# fpga-shield-v1_0.net
KiCad netlist of a schematic drawn in EAGLE
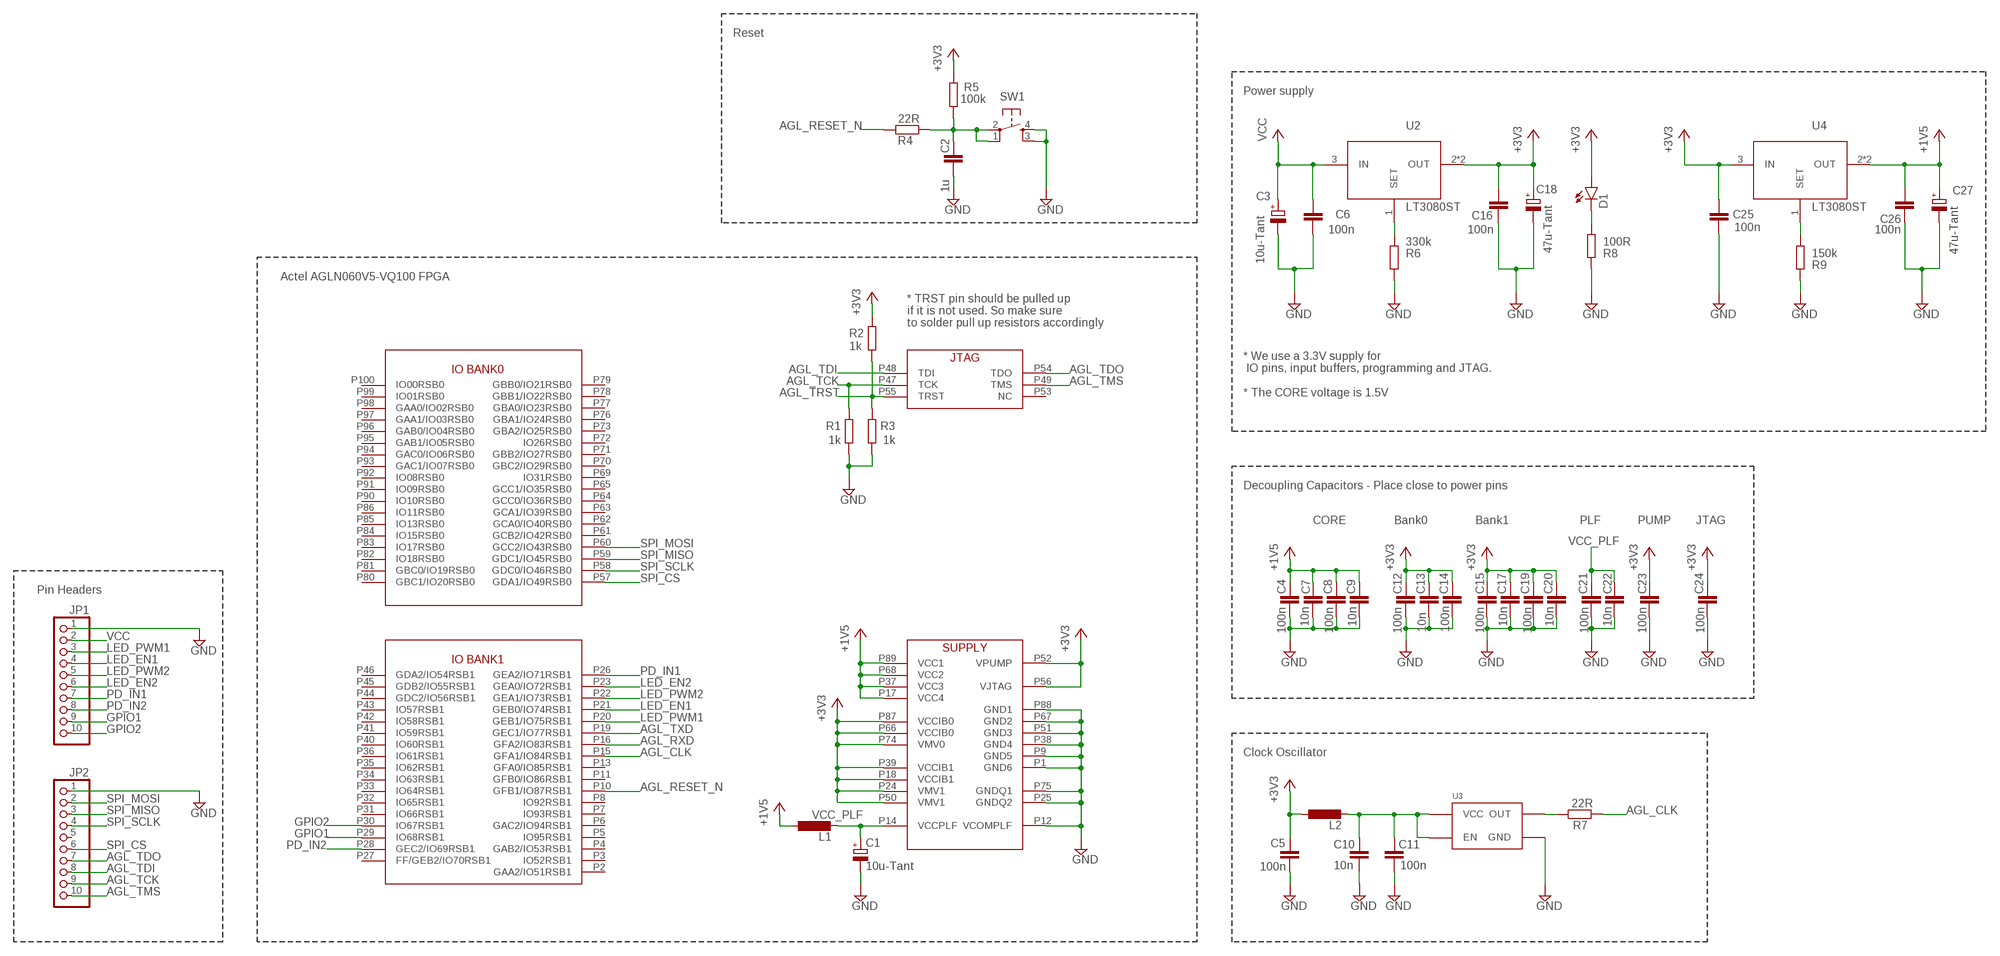
[diagram p0: schematic, sheet 1]

(export (version "E")
  (design (tool "Eeschema 10.0.6"))
  (components
    (comp (ref "C1")
      (value "10u-Tant")
      (footprint "eagle-import:CT3528")
      (libsource (lib "eagle-import") (part "CPOL-EUCT3528"))
    )
    (comp (ref "C2")
      (value "1u")
      (footprint "eagle-import:C0805")
      (libsource (lib "eagle-import") (part "C-EUC0805"))
    )
    (comp (ref "C3")
      (value "10u-Tant")
      (footprint "eagle-import:CT3528")
      (libsource (lib "eagle-import") (part "CPOL-EUCT3528"))
    )
    (comp (ref "C4")
      (value "100n")
      (footprint "eagle-import:C0805")
      (libsource (lib "eagle-import") (part "C-EUC0805"))
    )
    (comp (ref "C5")
      (value "100n")
      (footprint "eagle-import:C0805")
      (libsource (lib "eagle-import") (part "C-EUC0805"))
    )
    (comp (ref "C6")
      (value "100n")
      (footprint "eagle-import:C0805")
      (libsource (lib "eagle-import") (part "C-EUC0805"))
    )
    (comp (ref "C7")
      (value "10n")
      (footprint "eagle-import:C0805")
      (libsource (lib "eagle-import") (part "C-EUC0805"))
    )
    (comp (ref "C8")
      (value "100n")
      (footprint "eagle-import:C0805")
      (libsource (lib "eagle-import") (part "C-EUC0805"))
    )
    (comp (ref "C9")
      (value "10n")
      (footprint "eagle-import:C0805")
      (libsource (lib "eagle-import") (part "C-EUC0805"))
    )
    (comp (ref "C10")
      (value "10n")
      (footprint "eagle-import:C0805")
      (libsource (lib "eagle-import") (part "C-EUC0805"))
    )
    (comp (ref "C11")
      (value "100n")
      (footprint "eagle-import:C0805")
      (libsource (lib "eagle-import") (part "C-EUC0805"))
    )
    (comp (ref "C12")
      (value "100n")
      (footprint "eagle-import:C0805")
      (libsource (lib "eagle-import") (part "C-EUC0805"))
    )
    (comp (ref "C13")
      (value "10n")
      (footprint "eagle-import:C0805")
      (libsource (lib "eagle-import") (part "C-EUC0805"))
    )
    (comp (ref "C14")
      (value "100n")
      (footprint "eagle-import:C0805")
      (libsource (lib "eagle-import") (part "C-EUC0805"))
    )
    (comp (ref "C15")
      (value "100n")
      (footprint "eagle-import:C0805")
      (libsource (lib "eagle-import") (part "C-EUC0805"))
    )
    (comp (ref "C16")
      (value "100n")
      (footprint "eagle-import:C0805")
      (libsource (lib "eagle-import") (part "C-EUC0805"))
    )
    (comp (ref "C17")
      (value "10n")
      (footprint "eagle-import:C0805")
      (libsource (lib "eagle-import") (part "C-EUC0805"))
    )
    (comp (ref "C18")
      (value "47u-Tant")
      (footprint "eagle-import:CT3528")
      (libsource (lib "eagle-import") (part "CPOL-EUCT3528"))
    )
    (comp (ref "C19")
      (value "100n")
      (footprint "eagle-import:C0805")
      (libsource (lib "eagle-import") (part "C-EUC0805"))
    )
    (comp (ref "C20")
      (value "10n")
      (footprint "eagle-import:C0805")
      (libsource (lib "eagle-import") (part "C-EUC0805"))
    )
    (comp (ref "C21")
      (value "100n")
      (footprint "eagle-import:C0805")
      (libsource (lib "eagle-import") (part "C-EUC0805"))
    )
    (comp (ref "C22")
      (value "10n")
      (footprint "eagle-import:C0805")
      (libsource (lib "eagle-import") (part "C-EUC0805"))
    )
    (comp (ref "C23")
      (value "100n")
      (footprint "eagle-import:C0805")
      (libsource (lib "eagle-import") (part "C-EUC0805"))
    )
    (comp (ref "C24")
      (value "100n")
      (footprint "eagle-import:C0805")
      (libsource (lib "eagle-import") (part "C-EUC0805"))
    )
    (comp (ref "C25")
      (value "100n")
      (footprint "eagle-import:C0805")
      (libsource (lib "eagle-import") (part "C-EUC0805"))
    )
    (comp (ref "C26")
      (value "100n")
      (footprint "eagle-import:C0805")
      (libsource (lib "eagle-import") (part "C-EUC0805"))
    )
    (comp (ref "C27")
      (value "47u-Tant")
      (footprint "eagle-import:CT3528")
      (libsource (lib "eagle-import") (part "CPOL-EUCT3528"))
    )
    (comp (ref "D1")
      (value "LED0603")
      (footprint "eagle-import:LED-0603")
      (libsource (lib "eagle-import") (part "LED0603"))
    )
    (comp (ref "JP1")
      (value "PINHD-1X10")
      (footprint "eagle-import:1X10")
      (libsource (lib "eagle-import") (part "PINHD-1X10"))
    )
    (comp (ref "JP2")
      (value "PINHD-1X10")
      (footprint "eagle-import:1X10")
      (libsource (lib "eagle-import") (part "PINHD-1X10"))
    )
    (comp (ref "L1")
      (value "L-EUL3216C")
      (footprint "eagle-import:L3216C")
      (libsource (lib "eagle-import") (part "L-EUL3216C"))
    )
    (comp (ref "L2")
      (value "L-EUL3216C")
      (footprint "eagle-import:L3216C")
      (libsource (lib "eagle-import") (part "L-EUL3216C"))
    )
    (comp (ref "R1")
      (value "1k")
      (footprint "eagle-import:R0805")
      (libsource (lib "eagle-import") (part "R-EU_R0805"))
    )
    (comp (ref "R2")
      (value "1k")
      (footprint "eagle-import:R0805")
      (libsource (lib "eagle-import") (part "R-EU_R0805"))
    )
    (comp (ref "R3")
      (value "1k")
      (footprint "eagle-import:R0805")
      (libsource (lib "eagle-import") (part "R-EU_R0805"))
    )
    (comp (ref "R4")
      (value "22R")
      (footprint "eagle-import:R0805")
      (libsource (lib "eagle-import") (part "R-EU_R0805"))
    )
    (comp (ref "R5")
      (value "100k")
      (footprint "eagle-import:R0805")
      (libsource (lib "eagle-import") (part "R-EU_R0805"))
    )
    (comp (ref "R6")
      (value "330k")
      (footprint "eagle-import:R0805")
      (libsource (lib "eagle-import") (part "R-EU_R0805"))
    )
    (comp (ref "R7")
      (value "22R")
      (footprint "eagle-import:R0805")
      (libsource (lib "eagle-import") (part "R-EU_R0805"))
    )
    (comp (ref "R8")
      (value "100R")
      (footprint "eagle-import:R0805")
      (libsource (lib "eagle-import") (part "R-EU_R0805"))
    )
    (comp (ref "R9")
      (value "150k")
      (footprint "eagle-import:R0805")
      (libsource (lib "eagle-import") (part "R-EU_R0805"))
    )
    (comp (ref "SW1")
      (value "10-XX4X4SMD")
      (footprint "eagle-import:BT4X4")
      (libsource (lib "eagle-import") (part "10-XX4X4SMD"))
    )
    (comp (ref "U1")
      (value "AGLN060VQ100")
      (footprint "eagle-import:VQ100")
      (libsource (lib "eagle-import") (part "AGLN060VQ100"))
    )
    (comp (ref "U2")
      (value "LT3080ST")
      (footprint "eagle-import:SOT223")
      (libsource (lib "eagle-import") (part "LT3080ST"))
    )
    (comp (ref "U3")
      (value "ASFL1")
      (footprint "eagle-import:ASFL1")
      (libsource (lib "eagle-import") (part "ASFL1"))
    )
    (comp (ref "U4")
      (value "LT3080ST")
      (footprint "eagle-import:SOT223")
      (libsource (lib "eagle-import") (part "LT3080ST"))
    )
  )
  (nets
    (net (code "1") (name "+1V5") (class "Default")
      (node (ref "C26") (pin "1") (pinfunction "1_1") (pintype "passive"))
      (node (ref "C27") (pin "+") (pinfunction "+_+") (pintype "passive"))
      (node (ref "C4") (pin "1") (pinfunction "1_1") (pintype "passive"))
      (node (ref "C7") (pin "1") (pinfunction "1_1") (pintype "passive"))
      (node (ref "C8") (pin "1") (pinfunction "1_1") (pintype "passive"))
      (node (ref "C9") (pin "1") (pinfunction "1_1") (pintype "passive"))
      (node (ref "L1") (pin "1") (pinfunction "1_1") (pintype "passive"))
      (node (ref "U1") (pin "P17") (pinfunction "VCC4_P17") (pintype "power_in"))
      (node (ref "U1") (pin "P37") (pinfunction "VCC3_P37") (pintype "power_in"))
      (node (ref "U1") (pin "P68") (pinfunction "VCC2_P68") (pintype "power_in"))
      (node (ref "U1") (pin "P89") (pinfunction "VCC1_P89") (pintype "power_in"))
      (node (ref "U4") (pin "2") (pinfunction "OUT_2") (pintype "passive"))
      (node (ref "U4") (pin "4") (pinfunction "OUT_4") (pintype "passive"))
    )
    (net (code "2") (name "+3V3") (class "Default")
      (node (ref "C12") (pin "1") (pinfunction "1_1") (pintype "passive"))
      (node (ref "C13") (pin "1") (pinfunction "1_1") (pintype "passive"))
      (node (ref "C14") (pin "1") (pinfunction "1_1") (pintype "passive"))
      (node (ref "C15") (pin "1") (pinfunction "1_1") (pintype "passive"))
      (node (ref "C16") (pin "1") (pinfunction "1_1") (pintype "passive"))
      (node (ref "C17") (pin "1") (pinfunction "1_1") (pintype "passive"))
      (node (ref "C18") (pin "+") (pinfunction "+_+") (pintype "passive"))
      (node (ref "C19") (pin "1") (pinfunction "1_1") (pintype "passive"))
      (node (ref "C20") (pin "1") (pinfunction "1_1") (pintype "passive"))
      (node (ref "C23") (pin "1") (pinfunction "1_1") (pintype "passive"))
      (node (ref "C24") (pin "1") (pinfunction "1_1") (pintype "passive"))
      (node (ref "C25") (pin "1") (pinfunction "1_1") (pintype "passive"))
      (node (ref "C5") (pin "1") (pinfunction "1_1") (pintype "passive"))
      (node (ref "D1") (pin "A") (pinfunction "A_A") (pintype "passive"))
      (node (ref "L2") (pin "1") (pinfunction "1_1") (pintype "passive"))
      (node (ref "R2") (pin "2") (pinfunction "2_2") (pintype "passive"))
      (node (ref "R5") (pin "2") (pinfunction "2_2") (pintype "passive"))
      (node (ref "U1") (pin "P18") (pinfunction "VCCIB1_P18") (pintype "power_in"))
      (node (ref "U1") (pin "P24") (pinfunction "VMV1_P24") (pintype "power_in"))
      (node (ref "U1") (pin "P39") (pinfunction "VCCIB1_P39") (pintype "power_in"))
      (node (ref "U1") (pin "P50") (pinfunction "VMV1_P50") (pintype "power_in"))
      (node (ref "U1") (pin "P52") (pinfunction "VPUMP_P52") (pintype "power_in"))
      (node (ref "U1") (pin "P56") (pinfunction "VJTAG_P56") (pintype "power_in"))
      (node (ref "U1") (pin "P66") (pinfunction "VCCIB0_P66") (pintype "power_in"))
      (node (ref "U1") (pin "P74") (pinfunction "VMV0_P74") (pintype "power_in"))
      (node (ref "U1") (pin "P87") (pinfunction "VCCIB0_P87") (pintype "power_in"))
      (node (ref "U2") (pin "2") (pinfunction "OUT_2") (pintype "passive"))
      (node (ref "U2") (pin "4") (pinfunction "OUT_4") (pintype "passive"))
      (node (ref "U4") (pin "3") (pinfunction "IN_3") (pintype "power_in"))
    )
    (net (code "3") (name "/AGL_CLK") (class "Default")
      (node (ref "R7") (pin "2") (pinfunction "2_2") (pintype "passive"))
      (node (ref "U1") (pin "P15") (pinfunction "GFA1/IO84RSB1_P15") (pintype "bidirectional"))
    )
    (net (code "4") (name "/AGL_RESET_N") (class "Default")
      (node (ref "R4") (pin "2") (pinfunction "2_2") (pintype "passive"))
      (node (ref "U1") (pin "P10") (pinfunction "GFB1/IO87RSB1_P10") (pintype "bidirectional"))
    )
    (net (code "5") (name "/AGL_RXD") (class "Default")
      (node (ref "U1") (pin "P16") (pinfunction "GFA2/IO83RSB1_P16") (pintype "bidirectional"))
    )
    (net (code "6") (name "/AGL_TCK") (class "Default")
      (node (ref "JP2") (pin "9") (pinfunction "9_9") (pintype "passive"))
      (node (ref "R1") (pin "2") (pinfunction "2_2") (pintype "passive"))
      (node (ref "U1") (pin "P47") (pinfunction "TCK_P47") (pintype "input"))
    )
    (net (code "7") (name "/AGL_TDI") (class "Default")
      (node (ref "JP2") (pin "8") (pinfunction "8_8") (pintype "passive"))
      (node (ref "U1") (pin "P48") (pinfunction "TDI_P48") (pintype "input"))
    )
    (net (code "8") (name "/AGL_TDO") (class "Default")
      (node (ref "JP2") (pin "7") (pinfunction "7_7") (pintype "passive"))
      (node (ref "U1") (pin "P54") (pinfunction "TDO_P54") (pintype "output"))
    )
    (net (code "9") (name "/AGL_TMS") (class "Default")
      (node (ref "JP2") (pin "10") (pinfunction "10_10") (pintype "passive"))
      (node (ref "U1") (pin "P49") (pinfunction "TMS_P49") (pintype "input"))
    )
    (net (code "10") (name "/AGL_TRST") (class "Default")
      (node (ref "R2") (pin "1") (pinfunction "1_1") (pintype "passive"))
      (node (ref "R3") (pin "2") (pinfunction "2_2") (pintype "passive"))
      (node (ref "U1") (pin "P55") (pinfunction "TRST_P55") (pintype "input"))
    )
    (net (code "11") (name "/AGL_TXD") (class "Default")
      (node (ref "U1") (pin "P19") (pinfunction "GEC1/IO77RSB1_P19") (pintype "bidirectional"))
    )
    (net (code "12") (name "/GPIO1") (class "Default")
      (node (ref "JP1") (pin "9") (pinfunction "9_9") (pintype "passive"))
      (node (ref "U1") (pin "P29") (pinfunction "IO68RSB1_P29") (pintype "bidirectional"))
    )
    (net (code "13") (name "/GPIO2") (class "Default")
      (node (ref "JP1") (pin "10") (pinfunction "10_10") (pintype "passive"))
      (node (ref "U1") (pin "P30") (pinfunction "IO67RSB1_P30") (pintype "bidirectional"))
    )
    (net (code "14") (name "/LED_EN1") (class "Default")
      (node (ref "JP1") (pin "4") (pinfunction "4_4") (pintype "passive"))
      (node (ref "U1") (pin "P21") (pinfunction "GEB0/IO74RSB1_P21") (pintype "bidirectional"))
    )
    (net (code "15") (name "/LED_EN2") (class "Default")
      (node (ref "JP1") (pin "6") (pinfunction "6_6") (pintype "passive"))
      (node (ref "U1") (pin "P23") (pinfunction "GEA0/IO72RSB1_P23") (pintype "bidirectional"))
    )
    (net (code "16") (name "/LED_PWM1") (class "Default")
      (node (ref "JP1") (pin "3") (pinfunction "3_3") (pintype "passive"))
      (node (ref "U1") (pin "P20") (pinfunction "GEB1/IO75RSB1_P20") (pintype "bidirectional"))
    )
    (net (code "17") (name "/LED_PWM2") (class "Default")
      (node (ref "JP1") (pin "5") (pinfunction "5_5") (pintype "passive"))
      (node (ref "U1") (pin "P22") (pinfunction "GEA1/IO73RSB1_P22") (pintype "bidirectional"))
    )
    (net (code "18") (name "/PD_IN1") (class "Default")
      (node (ref "JP1") (pin "7") (pinfunction "7_7") (pintype "passive"))
      (node (ref "U1") (pin "P26") (pinfunction "GEA2/IO71RSB1_P26") (pintype "bidirectional"))
    )
    (net (code "19") (name "/PD_IN2") (class "Default")
      (node (ref "JP1") (pin "8") (pinfunction "8_8") (pintype "passive"))
      (node (ref "U1") (pin "P28") (pinfunction "GEC2/IO69RSB1_P28") (pintype "bidirectional"))
    )
    (net (code "20") (name "/SPI_CS") (class "Default")
      (node (ref "JP2") (pin "6") (pinfunction "6_6") (pintype "passive"))
      (node (ref "U1") (pin "P57") (pinfunction "GDA1/IO49RSB0_P57") (pintype "bidirectional"))
    )
    (net (code "21") (name "/SPI_MISO") (class "Default")
      (node (ref "JP2") (pin "3") (pinfunction "3_3") (pintype "passive"))
      (node (ref "U1") (pin "P59") (pinfunction "GDC1/IO45RSB0_P59") (pintype "bidirectional"))
    )
    (net (code "22") (name "/SPI_MOSI") (class "Default")
      (node (ref "JP2") (pin "2") (pinfunction "2_2") (pintype "passive"))
      (node (ref "U1") (pin "P60") (pinfunction "GCC2/IO43RSB0_P60") (pintype "bidirectional"))
    )
    (net (code "23") (name "/SPI_SCLK") (class "Default")
      (node (ref "JP2") (pin "4") (pinfunction "4_4") (pintype "passive"))
      (node (ref "U1") (pin "P58") (pinfunction "GDC0/IO46RSB0_P58") (pintype "bidirectional"))
    )
    (net (code "24") (name "/VCC_PLF") (class "Default")
      (node (ref "C1") (pin "+") (pinfunction "+_+") (pintype "passive"))
      (node (ref "C21") (pin "1") (pinfunction "1_1") (pintype "passive"))
      (node (ref "C22") (pin "1") (pinfunction "1_1") (pintype "passive"))
      (node (ref "L1") (pin "2") (pinfunction "2_2") (pintype "passive"))
      (node (ref "U1") (pin "P14") (pinfunction "VCCPLF_P14") (pintype "power_in"))
    )
    (net (code "25") (name "GND") (class "Default")
      (node (ref "C1") (pin "-") (pinfunction "-_-") (pintype "passive"))
      (node (ref "C10") (pin "2") (pinfunction "2_2") (pintype "passive"))
      (node (ref "C11") (pin "2") (pinfunction "2_2") (pintype "passive"))
      (node (ref "C12") (pin "2") (pinfunction "2_2") (pintype "passive"))
      (node (ref "C13") (pin "2") (pinfunction "2_2") (pintype "passive"))
      (node (ref "C14") (pin "2") (pinfunction "2_2") (pintype "passive"))
      (node (ref "C15") (pin "2") (pinfunction "2_2") (pintype "passive"))
      (node (ref "C16") (pin "2") (pinfunction "2_2") (pintype "passive"))
      (node (ref "C17") (pin "2") (pinfunction "2_2") (pintype "passive"))
      (node (ref "C18") (pin "-") (pinfunction "-_-") (pintype "passive"))
      (node (ref "C19") (pin "2") (pinfunction "2_2") (pintype "passive"))
      (node (ref "C2") (pin "2") (pinfunction "2_2") (pintype "passive"))
      (node (ref "C20") (pin "2") (pinfunction "2_2") (pintype "passive"))
      (node (ref "C21") (pin "2") (pinfunction "2_2") (pintype "passive"))
      (node (ref "C22") (pin "2") (pinfunction "2_2") (pintype "passive"))
      (node (ref "C23") (pin "2") (pinfunction "2_2") (pintype "passive"))
      (node (ref "C24") (pin "2") (pinfunction "2_2") (pintype "passive"))
      (node (ref "C25") (pin "2") (pinfunction "2_2") (pintype "passive"))
      (node (ref "C26") (pin "2") (pinfunction "2_2") (pintype "passive"))
      (node (ref "C27") (pin "-") (pinfunction "-_-") (pintype "passive"))
      (node (ref "C3") (pin "-") (pinfunction "-_-") (pintype "passive"))
      (node (ref "C4") (pin "2") (pinfunction "2_2") (pintype "passive"))
      (node (ref "C5") (pin "2") (pinfunction "2_2") (pintype "passive"))
      (node (ref "C6") (pin "2") (pinfunction "2_2") (pintype "passive"))
      (node (ref "C7") (pin "2") (pinfunction "2_2") (pintype "passive"))
      (node (ref "C8") (pin "2") (pinfunction "2_2") (pintype "passive"))
      (node (ref "C9") (pin "2") (pinfunction "2_2") (pintype "passive"))
      (node (ref "JP1") (pin "1") (pinfunction "1_1") (pintype "passive"))
      (node (ref "JP2") (pin "1") (pinfunction "1_1") (pintype "passive"))
      (node (ref "R1") (pin "1") (pinfunction "1_1") (pintype "passive"))
      (node (ref "R3") (pin "1") (pinfunction "1_1") (pintype "passive"))
      (node (ref "R6") (pin "2") (pinfunction "2_2") (pintype "passive"))
      (node (ref "R8") (pin "2") (pinfunction "2_2") (pintype "passive"))
      (node (ref "R9") (pin "2") (pinfunction "2_2") (pintype "passive"))
      (node (ref "SW1") (pin "3") (pinfunction "S1_3") (pintype "passive"))
      (node (ref "SW1") (pin "4") (pinfunction "S_4") (pintype "passive"))
      (node (ref "U1") (pin "P1") (pinfunction "GND6_P1") (pintype "power_in"))
      (node (ref "U1") (pin "P12") (pinfunction "VCOMPLF_P12") (pintype "power_in"))
      (node (ref "U1") (pin "P25") (pinfunction "GNDQ2_P25") (pintype "power_in"))
      (node (ref "U1") (pin "P38") (pinfunction "GND4_P38") (pintype "power_in"))
      (node (ref "U1") (pin "P51") (pinfunction "GND3_P51") (pintype "power_in"))
      (node (ref "U1") (pin "P67") (pinfunction "GND2_P67") (pintype "power_in"))
      (node (ref "U1") (pin "P75") (pinfunction "GNDQ1_P75") (pintype "power_in"))
      (node (ref "U1") (pin "P88") (pinfunction "GND1_P88") (pintype "power_in"))
      (node (ref "U1") (pin "P9") (pinfunction "GND5_P9") (pintype "power_in"))
      (node (ref "U3") (pin "P$2") (pinfunction "GND_P$2") (pintype "bidirectional"))
    )
    (net (code "26") (name "Net-(D1-PadC)") (class "Default")
      (node (ref "D1") (pin "C") (pinfunction "C_C") (pintype "passive"))
      (node (ref "R8") (pin "1") (pinfunction "1_1") (pintype "passive"))
    )
    (net (code "27") (name "Net-(SW1-P)") (class "Default")
      (node (ref "C2") (pin "1") (pinfunction "1_1") (pintype "passive"))
      (node (ref "R4") (pin "1") (pinfunction "1_1") (pintype "passive"))
      (node (ref "R5") (pin "1") (pinfunction "1_1") (pintype "passive"))
      (node (ref "SW1") (pin "1") (pinfunction "P1_1") (pintype "passive"))
      (node (ref "SW1") (pin "2") (pinfunction "P_2") (pintype "passive"))
    )
    (net (code "28") (name "Net-(U2-SET)") (class "Default")
      (node (ref "R6") (pin "1") (pinfunction "1_1") (pintype "passive"))
      (node (ref "U2") (pin "1") (pinfunction "SET_1") (pintype "passive"))
    )
    (net (code "29") (name "Net-(U3-EN)") (class "Default")
      (node (ref "C10") (pin "1") (pinfunction "1_1") (pintype "passive"))
      (node (ref "C11") (pin "1") (pinfunction "1_1") (pintype "passive"))
      (node (ref "L2") (pin "2") (pinfunction "2_2") (pintype "passive"))
      (node (ref "U3") (pin "P$1") (pinfunction "EN_P$1") (pintype "bidirectional"))
      (node (ref "U3") (pin "P$4") (pinfunction "VCC_P$4") (pintype "bidirectional"))
    )
    (net (code "30") (name "Net-(U3-OUT)") (class "Default")
      (node (ref "R7") (pin "1") (pinfunction "1_1") (pintype "passive"))
      (node (ref "U3") (pin "P$3") (pinfunction "OUT_P$3") (pintype "bidirectional"))
    )
    (net (code "31") (name "Net-(U4-SET)") (class "Default")
      (node (ref "R9") (pin "1") (pinfunction "1_1") (pintype "passive"))
      (node (ref "U4") (pin "1") (pinfunction "SET_1") (pintype "passive"))
    )
    (net (code "32") (name "VCC") (class "Default")
      (node (ref "C3") (pin "+") (pinfunction "+_+") (pintype "passive"))
      (node (ref "C6") (pin "1") (pinfunction "1_1") (pintype "passive"))
      (node (ref "JP1") (pin "2") (pinfunction "2_2") (pintype "passive"))
      (node (ref "U2") (pin "3") (pinfunction "IN_3") (pintype "power_in"))
    )
    (net (code "33") (name "unconnected-(JP2-Pad5)") (class "Default")
      (node (ref "JP2") (pin "5") (pinfunction "5_5") (pintype "passive"))
    )
    (net (code "34") (name "unconnected-(U1A-GAA0{slash}IO02RSB0-PadP98)") (class "Default")
      (node (ref "U1") (pin "P98") (pinfunction "GAA0/IO02RSB0_P98") (pintype "bidirectional"))
    )
    (net (code "35") (name "unconnected-(U1A-GAA1{slash}IO03RSB0-PadP97)") (class "Default")
      (node (ref "U1") (pin "P97") (pinfunction "GAA1/IO03RSB0_P97") (pintype "bidirectional"))
    )
    (net (code "36") (name "unconnected-(U1A-GAB0{slash}IO04RSB0-PadP96)") (class "Default")
      (node (ref "U1") (pin "P96") (pinfunction "GAB0/IO04RSB0_P96") (pintype "bidirectional"))
    )
    (net (code "37") (name "unconnected-(U1A-GAB1{slash}IO05RSB0-PadP95)") (class "Default")
      (node (ref "U1") (pin "P95") (pinfunction "GAB1/IO05RSB0_P95") (pintype "bidirectional"))
    )
    (net (code "38") (name "unconnected-(U1A-GAC0{slash}IO06RSB0-PadP94)") (class "Default")
      (node (ref "U1") (pin "P94") (pinfunction "GAC0/IO06RSB0_P94") (pintype "bidirectional"))
    )
    (net (code "39") (name "unconnected-(U1A-GAC1{slash}IO07RSB0-PadP93)") (class "Default")
      (node (ref "U1") (pin "P93") (pinfunction "GAC1/IO07RSB0_P93") (pintype "bidirectional"))
    )
    (net (code "40") (name "unconnected-(U1A-GBA0{slash}IO23RSB0-PadP77)") (class "Default")
      (node (ref "U1") (pin "P77") (pinfunction "GBA0/IO23RSB0_P77") (pintype "bidirectional"))
    )
    (net (code "41") (name "unconnected-(U1A-GBA1{slash}IO24RSB0-PadP76)") (class "Default")
      (node (ref "U1") (pin "P76") (pinfunction "GBA1/IO24RSB0_P76") (pintype "bidirectional"))
    )
    (net (code "42") (name "unconnected-(U1A-GBA2{slash}IO25RSB0-PadP73)") (class "Default")
      (node (ref "U1") (pin "P73") (pinfunction "GBA2/IO25RSB0_P73") (pintype "bidirectional"))
    )
    (net (code "43") (name "unconnected-(U1A-GBB0{slash}IO21RSB0-PadP79)") (class "Default")
      (node (ref "U1") (pin "P79") (pinfunction "GBB0/IO21RSB0_P79") (pintype "bidirectional"))
    )
    (net (code "44") (name "unconnected-(U1A-GBB1{slash}IO22RSB0-PadP78)") (class "Default")
      (node (ref "U1") (pin "P78") (pinfunction "GBB1/IO22RSB0_P78") (pintype "bidirectional"))
    )
    (net (code "45") (name "unconnected-(U1A-GBB2{slash}IO27RSB0-PadP71)") (class "Default")
      (node (ref "U1") (pin "P71") (pinfunction "GBB2/IO27RSB0_P71") (pintype "bidirectional"))
    )
    (net (code "46") (name "unconnected-(U1A-GBC0{slash}IO19RSB0-PadP81)") (class "Default")
      (node (ref "U1") (pin "P81") (pinfunction "GBC0/IO19RSB0_P81") (pintype "bidirectional"))
    )
    (net (code "47") (name "unconnected-(U1A-GBC1{slash}IO20RSB0-PadP80)") (class "Default")
      (node (ref "U1") (pin "P80") (pinfunction "GBC1/IO20RSB0_P80") (pintype "bidirectional"))
    )
    (net (code "48") (name "unconnected-(U1A-GBC2{slash}IO29RSB0-PadP70)") (class "Default")
      (node (ref "U1") (pin "P70") (pinfunction "GBC2/IO29RSB0_P70") (pintype "bidirectional"))
    )
    (net (code "49") (name "unconnected-(U1A-GCA0{slash}IO40RSB0-PadP62)") (class "Default")
      (node (ref "U1") (pin "P62") (pinfunction "GCA0/IO40RSB0_P62") (pintype "bidirectional"))
    )
    (net (code "50") (name "unconnected-(U1A-GCA1{slash}IO39RSB0-PadP63)") (class "Default")
      (node (ref "U1") (pin "P63") (pinfunction "GCA1/IO39RSB0_P63") (pintype "bidirectional"))
    )
    (net (code "51") (name "unconnected-(U1A-GCB2{slash}IO42RSB0-PadP61)") (class "Default")
      (node (ref "U1") (pin "P61") (pinfunction "GCB2/IO42RSB0_P61") (pintype "bidirectional"))
    )
    (net (code "52") (name "unconnected-(U1A-GCC0{slash}IO36RSB0-PadP64)") (class "Default")
      (node (ref "U1") (pin "P64") (pinfunction "GCC0/IO36RSB0_P64") (pintype "bidirectional"))
    )
    (net (code "53") (name "unconnected-(U1A-GCC1{slash}IO35RSB0-PadP65)") (class "Default")
      (node (ref "U1") (pin "P65") (pinfunction "GCC1/IO35RSB0_P65") (pintype "bidirectional"))
    )
    (net (code "54") (name "unconnected-(U1A-IO00RSB0-PadP100)") (class "Default")
      (node (ref "U1") (pin "P100") (pinfunction "IO00RSB0_P100") (pintype "bidirectional"))
    )
    (net (code "55") (name "unconnected-(U1A-IO01RSB0-PadP99)") (class "Default")
      (node (ref "U1") (pin "P99") (pinfunction "IO01RSB0_P99") (pintype "bidirectional"))
    )
    (net (code "56") (name "unconnected-(U1A-IO08RSB0-PadP92)") (class "Default")
      (node (ref "U1") (pin "P92") (pinfunction "IO08RSB0_P92") (pintype "bidirectional"))
    )
    (net (code "57") (name "unconnected-(U1A-IO09RSB0-PadP91)") (class "Default")
      (node (ref "U1") (pin "P91") (pinfunction "IO09RSB0_P91") (pintype "bidirectional"))
    )
    (net (code "58") (name "unconnected-(U1A-IO10RSB0-PadP90)") (class "Default")
      (node (ref "U1") (pin "P90") (pinfunction "IO10RSB0_P90") (pintype "bidirectional"))
    )
    (net (code "59") (name "unconnected-(U1A-IO11RSB0-PadP86)") (class "Default")
      (node (ref "U1") (pin "P86") (pinfunction "IO11RSB0_P86") (pintype "bidirectional"))
    )
    (net (code "60") (name "unconnected-(U1A-IO13RSB0-PadP85)") (class "Default")
      (node (ref "U1") (pin "P85") (pinfunction "IO13RSB0_P85") (pintype "bidirectional"))
    )
    (net (code "61") (name "unconnected-(U1A-IO15RSB0-PadP84)") (class "Default")
      (node (ref "U1") (pin "P84") (pinfunction "IO15RSB0_P84") (pintype "bidirectional"))
    )
    (net (code "62") (name "unconnected-(U1A-IO17RSB0-PadP83)") (class "Default")
      (node (ref "U1") (pin "P83") (pinfunction "IO17RSB0_P83") (pintype "bidirectional"))
    )
    (net (code "63") (name "unconnected-(U1A-IO18RSB0-PadP82)") (class "Default")
      (node (ref "U1") (pin "P82") (pinfunction "IO18RSB0_P82") (pintype "bidirectional"))
    )
    (net (code "64") (name "unconnected-(U1A-IO26RSB0-PadP72)") (class "Default")
      (node (ref "U1") (pin "P72") (pinfunction "IO26RSB0_P72") (pintype "bidirectional"))
    )
    (net (code "65") (name "unconnected-(U1A-IO31RSB0-PadP69)") (class "Default")
      (node (ref "U1") (pin "P69") (pinfunction "IO31RSB0_P69") (pintype "bidirectional"))
    )
    (net (code "66") (name "unconnected-(U1B-FF{slash}GEB2{slash}IO70RSB1-PadP27)") (class "Default")
      (node (ref "U1") (pin "P27") (pinfunction "FF/GEB2/IO70RSB1_P27") (pintype "bidirectional"))
    )
    (net (code "67") (name "unconnected-(U1B-GAA2{slash}IO51RSB1-PadP2)") (class "Default")
      (node (ref "U1") (pin "P2") (pinfunction "GAA2/IO51RSB1_P2") (pintype "bidirectional"))
    )
    (net (code "68") (name "unconnected-(U1B-GAB2{slash}IO53RSB1-PadP4)") (class "Default")
      (node (ref "U1") (pin "P4") (pinfunction "GAB2/IO53RSB1_P4") (pintype "bidirectional"))
    )
    (net (code "69") (name "unconnected-(U1B-GAC2{slash}IO94RSB1-PadP6)") (class "Default")
      (node (ref "U1") (pin "P6") (pinfunction "GAC2/IO94RSB1_P6") (pintype "bidirectional"))
    )
    (net (code "70") (name "unconnected-(U1B-GDA2{slash}IO54RSB1-PadP46)") (class "Default")
      (node (ref "U1") (pin "P46") (pinfunction "GDA2/IO54RSB1_P46") (pintype "bidirectional"))
    )
    (net (code "71") (name "unconnected-(U1B-GDB2{slash}IO55RSB1-PadP45)") (class "Default")
      (node (ref "U1") (pin "P45") (pinfunction "GDB2/IO55RSB1_P45") (pintype "bidirectional"))
    )
    (net (code "72") (name "unconnected-(U1B-GDC2{slash}IO56RSB1-PadP44)") (class "Default")
      (node (ref "U1") (pin "P44") (pinfunction "GDC2/IO56RSB1_P44") (pintype "bidirectional"))
    )
    (net (code "73") (name "unconnected-(U1B-GFA0{slash}IO85RSB1-PadP13)") (class "Default")
      (node (ref "U1") (pin "P13") (pinfunction "GFA0/IO85RSB1_P13") (pintype "bidirectional"))
    )
    (net (code "74") (name "unconnected-(U1B-GFB0{slash}IO86RSB1-PadP11)") (class "Default")
      (node (ref "U1") (pin "P11") (pinfunction "GFB0/IO86RSB1_P11") (pintype "bidirectional"))
    )
    (net (code "75") (name "unconnected-(U1B-IO52RSB1-PadP3)") (class "Default")
      (node (ref "U1") (pin "P3") (pinfunction "IO52RSB1_P3") (pintype "bidirectional"))
    )
    (net (code "76") (name "unconnected-(U1B-IO57RSB1-PadP43)") (class "Default")
      (node (ref "U1") (pin "P43") (pinfunction "IO57RSB1_P43") (pintype "bidirectional"))
    )
    (net (code "77") (name "unconnected-(U1B-IO58RSB1-PadP42)") (class "Default")
      (node (ref "U1") (pin "P42") (pinfunction "IO58RSB1_P42") (pintype "bidirectional"))
    )
    (net (code "78") (name "unconnected-(U1B-IO59RSB1-PadP41)") (class "Default")
      (node (ref "U1") (pin "P41") (pinfunction "IO59RSB1_P41") (pintype "bidirectional"))
    )
    (net (code "79") (name "unconnected-(U1B-IO60RSB1-PadP40)") (class "Default")
      (node (ref "U1") (pin "P40") (pinfunction "IO60RSB1_P40") (pintype "bidirectional"))
    )
    (net (code "80") (name "unconnected-(U1B-IO61RSB1-PadP36)") (class "Default")
      (node (ref "U1") (pin "P36") (pinfunction "IO61RSB1_P36") (pintype "bidirectional"))
    )
    (net (code "81") (name "unconnected-(U1B-IO62RSB1-PadP35)") (class "Default")
      (node (ref "U1") (pin "P35") (pinfunction "IO62RSB1_P35") (pintype "bidirectional"))
    )
    (net (code "82") (name "unconnected-(U1B-IO63RSB1-PadP34)") (class "Default")
      (node (ref "U1") (pin "P34") (pinfunction "IO63RSB1_P34") (pintype "bidirectional"))
    )
    (net (code "83") (name "unconnected-(U1B-IO64RSB1-PadP33)") (class "Default")
      (node (ref "U1") (pin "P33") (pinfunction "IO64RSB1_P33") (pintype "bidirectional"))
    )
    (net (code "84") (name "unconnected-(U1B-IO65RSB1-PadP32)") (class "Default")
      (node (ref "U1") (pin "P32") (pinfunction "IO65RSB1_P32") (pintype "bidirectional"))
    )
    (net (code "85") (name "unconnected-(U1B-IO66RSB1-PadP31)") (class "Default")
      (node (ref "U1") (pin "P31") (pinfunction "IO66RSB1_P31") (pintype "bidirectional"))
    )
    (net (code "86") (name "unconnected-(U1B-IO92RSB1-PadP8)") (class "Default")
      (node (ref "U1") (pin "P8") (pinfunction "IO92RSB1_P8") (pintype "bidirectional"))
    )
    (net (code "87") (name "unconnected-(U1B-IO93RSB1-PadP7)") (class "Default")
      (node (ref "U1") (pin "P7") (pinfunction "IO93RSB1_P7") (pintype "bidirectional"))
    )
    (net (code "88") (name "unconnected-(U1B-IO95RSB1-PadP5)") (class "Default")
      (node (ref "U1") (pin "P5") (pinfunction "IO95RSB1_P5") (pintype "bidirectional"))
    )
    (net (code "89") (name "unconnected-(U1C-NC-PadP53)") (class "Default")
      (node (ref "U1") (pin "P53") (pinfunction "NC_P53") (pintype "no_connect"))
    )
  )
)
